# Boost_stage_closed_loop.net
KiCad netlist of a schematic drawn in Altium Designer
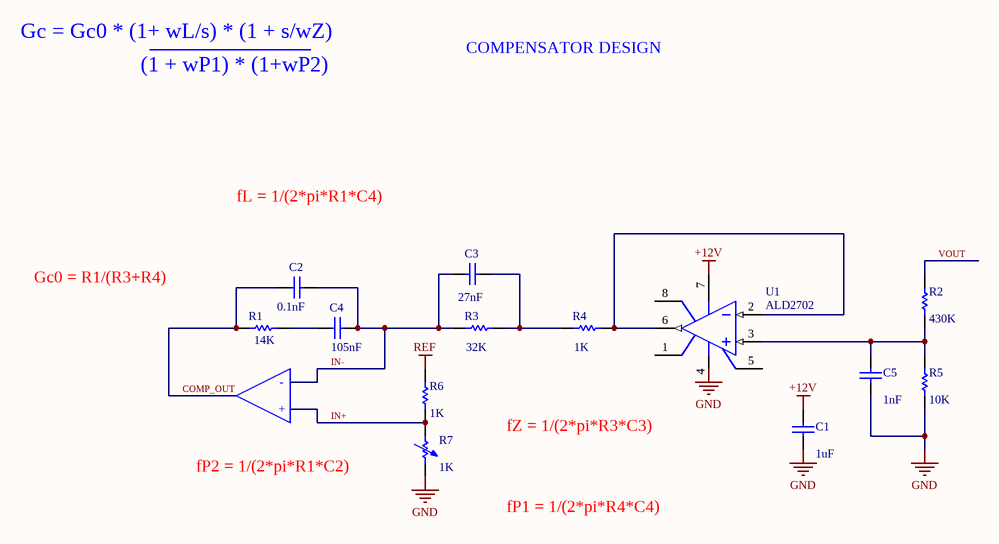
[diagram p0: Boost_stage_closed_loop.SchDoc]

(export (version "E")
  (design (tool "Eeschema 10.0.6"))
  (components
    (comp (ref "C1")
      (value "1uF")
      (footprint "RAD-0.3")
      (description "Capacitor")
      (fields (field (name "PUBLISHER") "Altium Limited"))
      (libsource (lib "Miscellaneous Devices") (part "Cap"))
    )
    (comp (ref "C2")
      (value "0.1nF")
      (footprint "RAD-0.3")
      (description "Capacitor")
      (fields (field (name "PUBLISHER") "Altium Limited"))
      (libsource (lib "Miscellaneous Devices") (part "Cap"))
    )
    (comp (ref "C3")
      (value "27nF")
      (footprint "RAD-0.3")
      (description "Capacitor")
      (fields (field (name "PUBLISHER") "Altium Limited"))
      (libsource (lib "Miscellaneous Devices") (part "Cap"))
    )
    (comp (ref "C4")
      (value "105nF")
      (footprint "RAD-0.3")
      (description "Capacitor")
      (fields (field (name "PUBLISHER") "Altium Limited"))
      (libsource (lib "Miscellaneous Devices") (part "Cap"))
    )
    (comp (ref "C5")
      (value "1nF")
      (footprint "RAD-0.3")
      (description "Capacitor")
      (fields (field (name "PUBLISHER") "Altium Limited"))
      (libsource (lib "Miscellaneous Devices") (part "Cap"))
    )
    (comp (ref "R1")
      (value "14K")
      (footprint "AXIAL-0.3")
      (description "Resistor")
      (fields (field (name "PUBLISHER") "Altium Limited"))
      (libsource (lib "Miscellaneous Devices") (part "Res1"))
    )
    (comp (ref "R2")
      (value "430K")
      (footprint "AXIAL-0.3")
      (description "Resistor")
      (fields (field (name "PUBLISHER") "Altium Limited"))
      (libsource (lib "Miscellaneous Devices") (part "Res1"))
    )
    (comp (ref "R3")
      (value "32K")
      (footprint "AXIAL-0.3")
      (description "Resistor")
      (fields (field (name "PUBLISHER") "Altium Limited"))
      (libsource (lib "Miscellaneous Devices") (part "Res1"))
    )
    (comp (ref "R4")
      (value "1K")
      (footprint "AXIAL-0.3")
      (description "Resistor")
      (fields (field (name "PUBLISHER") "Altium Limited"))
      (libsource (lib "Miscellaneous Devices") (part "Res1"))
    )
    (comp (ref "R5")
      (value "10K")
      (footprint "AXIAL-0.3")
      (description "Resistor")
      (fields (field (name "PUBLISHER") "Altium Limited"))
      (libsource (lib "Miscellaneous Devices") (part "Res1"))
    )
    (comp (ref "R6")
      (value "1K")
      (footprint "AXIAL-0.3")
      (description "Resistor")
      (fields (field (name "PUBLISHER") "Altium Limited"))
      (libsource (lib "Miscellaneous Devices") (part "Res1"))
    )
    (comp (ref "R7")
      (value "1K")
      (footprint "AXIAL-0.7")
      (description "Variable Resistor")
      (fields (field (name "Comment") "Res Adj1") (field (name "PUBLISHER") "Altium Limited"))
      (libsource (lib "Miscellaneous Devices") (part "Res Adj1"))
    )
    (comp (ref "U1")
      (value "ALD2702")
      (footprint "H-08A")
      (description "FET Operational Amplifier")
      (fields (field (name "PUBLISHER") "Altium Limited"))
      (libsource (lib "Miscellaneous Devices") (part "Op Amp"))
    )
  )
  (nets
    (net (code "1") (name "+12V") (class "Default")
      (node (ref "C1") (pin "1") (pinfunction "1_1") (pintype "passive"))
      (node (ref "U1") (pin "7") (pinfunction "V+_7") (pintype "power_in"))
    )
    (net (code "2") (name "/COMP_OUT") (class "Default")
      (node (ref "C2") (pin "2") (pinfunction "2_2") (pintype "passive"))
      (node (ref "R1") (pin "2") (pinfunction "2_2") (pintype "passive"))
    )
    (net (code "3") (name "/IN+") (class "Default")
      (node (ref "R6") (pin "2") (pinfunction "2_2") (pintype "passive"))
      (node (ref "R7") (pin "1") (pinfunction "1_1") (pintype "passive"))
    )
    (net (code "4") (name "/IN-") (class "Default")
      (node (ref "C2") (pin "1") (pinfunction "1_1") (pintype "passive"))
      (node (ref "C3") (pin "1") (pinfunction "1_1") (pintype "passive"))
      (node (ref "C4") (pin "1") (pinfunction "1_1") (pintype "passive"))
      (node (ref "R3") (pin "2") (pinfunction "2_2") (pintype "passive"))
    )
    (net (code "5") (name "/VOUT") (class "Default")
      (node (ref "R2") (pin "2") (pinfunction "2_2") (pintype "passive"))
    )
    (net (code "6") (name "GND") (class "Default")
      (node (ref "C1") (pin "2") (pinfunction "2_2") (pintype "passive"))
      (node (ref "C5") (pin "1") (pinfunction "1_1") (pintype "passive"))
      (node (ref "R5") (pin "1") (pinfunction "1_1") (pintype "passive"))
      (node (ref "R7") (pin "2") (pinfunction "2_2") (pintype "passive"))
    )
    (net (code "7") (name "Net-(C3-Pad2)") (class "Default")
      (node (ref "C3") (pin "2") (pinfunction "2_2") (pintype "passive"))
      (node (ref "R3") (pin "1") (pinfunction "1_1") (pintype "passive"))
      (node (ref "R4") (pin "2") (pinfunction "2_2") (pintype "passive"))
    )
    (net (code "8") (name "Net-(C4-Pad2)") (class "Default")
      (node (ref "C4") (pin "2") (pinfunction "2_2") (pintype "passive"))
      (node (ref "R1") (pin "1") (pinfunction "1_1") (pintype "passive"))
    )
    (net (code "9") (name "Net-(U1-IN+)") (class "Default")
      (node (ref "C5") (pin "2") (pinfunction "2_2") (pintype "passive"))
      (node (ref "R2") (pin "1") (pinfunction "1_1") (pintype "passive"))
      (node (ref "R5") (pin "2") (pinfunction "2_2") (pintype "passive"))
      (node (ref "U1") (pin "3") (pinfunction "IN+_3") (pintype "input"))
    )
    (net (code "10") (name "Net-(U1-IN-)") (class "Default")
      (node (ref "R4") (pin "1") (pinfunction "1_1") (pintype "passive"))
      (node (ref "U1") (pin "2") (pinfunction "IN-_2") (pintype "input"))
      (node (ref "U1") (pin "6") (pinfunction "OUT_6") (pintype "output"))
    )
    (net (code "11") (name "REF") (class "Default")
      (node (ref "R6") (pin "1") (pinfunction "1_1") (pintype "passive"))
    )
    (net (code "12") (name "unconnected-(U1-OS_NUL-Pad1)") (class "Default")
      (node (ref "U1") (pin "1") (pinfunction "OS_NUL_1") (pintype "passive"))
    )
    (net (code "13") (name "unconnected-(U1-OS_NUL-Pad5)") (class "Default")
      (node (ref "U1") (pin "5") (pinfunction "OS_NUL_5") (pintype "passive"))
    )
    (net (code "14") (name "unconnected-(U1-TAB-Pad8)") (class "Default")
      (node (ref "U1") (pin "8") (pinfunction "TAB_8") (pintype "passive"))
    )
    (net (code "15") (name "unconnected-(U1-V--Pad4)") (class "Default")
      (node (ref "U1") (pin "4") (pinfunction "V-_4") (pintype "power_in"))
    )
  )
)
